# AtmegaSwitch.net
KiCad netlist of a schematic drawn in EAGLE
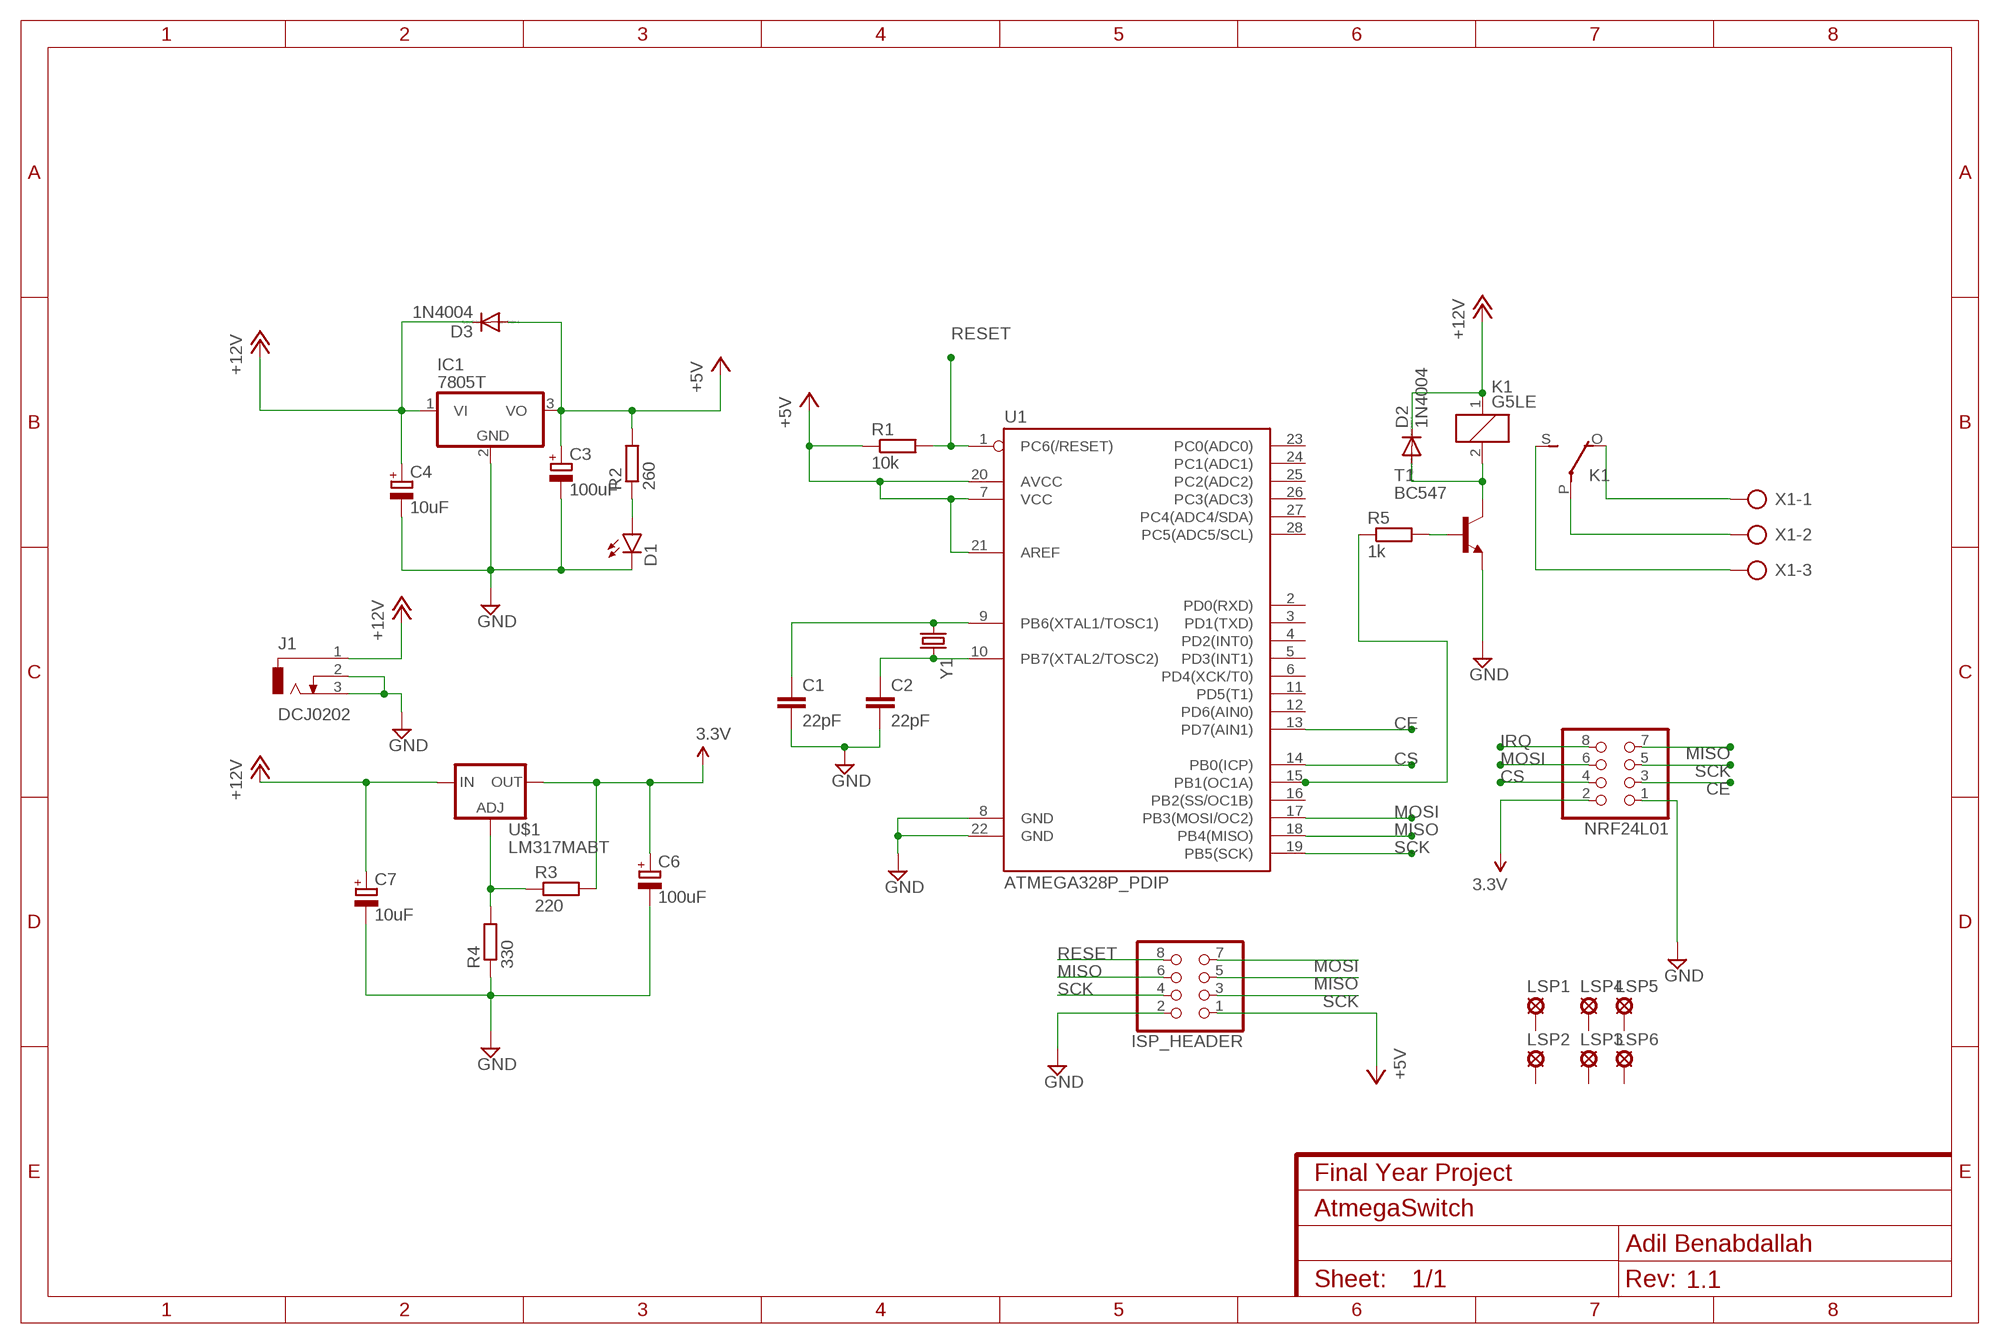
[diagram p0: schematic, sheet 1]

(export (version "E")
  (design (tool "Eeschema 10.0.6"))
  (components
    (comp (ref "C1")
      (value "22pF")
      (footprint "eagle-import:C025-025X050")
      (libsource (lib "eagle-import") (part "resistor_C-EU025-025X050"))
    )
    (comp (ref "C2")
      (value "22pF")
      (footprint "eagle-import:C025-024X044")
      (libsource (lib "eagle-import") (part "C-EU025-024X044"))
    )
    (comp (ref "C3")
      (value "100uF")
      (footprint "eagle-import:E5-6")
      (libsource (lib "eagle-import") (part "CPOL-EUE5-6"))
    )
    (comp (ref "C4")
      (value "10uF")
      (footprint "eagle-import:E5-6")
      (libsource (lib "eagle-import") (part "CPOL-EUE5-6"))
    )
    (comp (ref "C6")
      (value "100uF")
      (footprint "eagle-import:E5-6")
      (libsource (lib "eagle-import") (part "CPOL-EUE5-6"))
    )
    (comp (ref "C7")
      (value "10uF")
      (footprint "eagle-import:E5-6")
      (libsource (lib "eagle-import") (part "CPOL-EUE5-6"))
    )
    (comp (ref "D1")
      (value "LED5MM")
      (footprint "eagle-import:LED5MM")
      (libsource (lib "eagle-import") (part "LED5MM"))
    )
    (comp (ref "D2")
      (value "1N4004")
      (footprint "eagle-import:DO41-10")
      (libsource (lib "eagle-import") (part "1N4004"))
    )
    (comp (ref "D3")
      (value "1N4004")
      (footprint "eagle-import:DO41-10")
      (libsource (lib "eagle-import") (part "1N4004"))
    )
    (comp (ref "IC1")
      (value "7805T")
      (footprint "eagle-import:TO220H")
      (libsource (lib "eagle-import") (part "78T05"))
    )
    (comp (ref "ISP_HEADER")
      (value "PINHD-2X4")
      (footprint "eagle-import:2X04")
      (libsource (lib "eagle-import") (part "PINHD-2X4"))
    )
    (comp (ref "J1")
      (value "DCJ0202")
      (footprint "eagle-import:DCJ0202")
      (libsource (lib "eagle-import") (part "DCJ0202"))
    )
    (comp (ref "K1")
      (value "G5LE")
      (footprint "eagle-import:G5LE")
      (libsource (lib "eagle-import") (part "G5LE"))
    )
    (comp (ref "LSP1")
      (value "LSP10")
      (footprint "eagle-import:LSP10")
      (libsource (lib "eagle-import") (part "LSP10"))
    )
    (comp (ref "LSP2")
      (value "LSP10")
      (footprint "eagle-import:LSP10")
      (libsource (lib "eagle-import") (part "LSP10"))
    )
    (comp (ref "LSP3")
      (value "LSP10")
      (footprint "eagle-import:LSP10")
      (libsource (lib "eagle-import") (part "LSP10"))
    )
    (comp (ref "LSP4")
      (value "LSP10")
      (footprint "eagle-import:LSP10")
      (libsource (lib "eagle-import") (part "LSP10"))
    )
    (comp (ref "LSP5")
      (value "LSP10")
      (footprint "eagle-import:LSP10")
      (libsource (lib "eagle-import") (part "LSP10"))
    )
    (comp (ref "LSP6")
      (value "LSP10")
      (footprint "eagle-import:LSP10")
      (libsource (lib "eagle-import") (part "LSP10"))
    )
    (comp (ref "NRF24L01")
      (value "PINHD-2X4")
      (footprint "eagle-import:2X04")
      (libsource (lib "eagle-import") (part "PINHD-2X4"))
    )
    (comp (ref "R1")
      (value "10k")
      (footprint "eagle-import:0204_7")
      (libsource (lib "eagle-import") (part "R-EU_0204/7"))
    )
    (comp (ref "R2")
      (value "260")
      (footprint "eagle-import:0204_7")
      (libsource (lib "eagle-import") (part "R-EU_0204/7"))
    )
    (comp (ref "R3")
      (value "220")
      (footprint "eagle-import:0204_7")
      (libsource (lib "eagle-import") (part "R-EU_0204/7"))
    )
    (comp (ref "R4")
      (value "330")
      (footprint "eagle-import:0204_7")
      (libsource (lib "eagle-import") (part "R-EU_0204/7"))
    )
    (comp (ref "R5")
      (value "1k")
      (footprint "eagle-import:0204_7")
      (libsource (lib "eagle-import") (part "R-EU_0204/7"))
    )
    (comp (ref "T1")
      (value "BC547")
      (footprint "eagle-import:TO92")
      (libsource (lib "eagle-import") (part "BC547"))
    )
    (comp (ref "U$1")
      (value "LM317MABT")
      (footprint "eagle-import:TO220L1")
      (libsource (lib "eagle-import") (part "LM317?MABT"))
    )
    (comp (ref "U1")
      (value "ATMEGA328P_PDIP")
      (footprint "eagle-import:DIL28-3")
      (libsource (lib "eagle-import") (part "ATMEGA328P_PDIP"))
    )
    (comp (ref "X1")
      (value "AK500/3-H")
      (footprint "eagle-import:AK500_3-H")
      (libsource (lib "eagle-import") (part "AK500/3-H"))
    )
    (comp (ref "Y1")
      (value "CRYSTALHC49US")
      (footprint "eagle-import:HC49US")
      (libsource (lib "eagle-import") (part "CRYSTALHC49US"))
    )
  )
  (nets
    (net (code "1") (name "+5V") (class "Default")
      (node (ref "C3") (pin "+") (pinfunction "+_+") (pintype "passive"))
      (node (ref "D3") (pin "A") (pinfunction "A_A") (pintype "passive"))
      (node (ref "IC1") (pin "3") (pinfunction "VO_3") (pintype "passive"))
      (node (ref "ISP_HEADER") (pin "1") (pinfunction "1_1") (pintype "passive"))
      (node (ref "R1") (pin "1") (pinfunction "1_1") (pintype "passive"))
      (node (ref "R2") (pin "2") (pinfunction "2_2") (pintype "passive"))
      (node (ref "U1") (pin "20") (pinfunction "AVCC_20") (pintype "bidirectional"))
      (node (ref "U1") (pin "21") (pinfunction "AREF_21") (pintype "bidirectional"))
      (node (ref "U1") (pin "7") (pinfunction "VCC_7") (pintype "bidirectional"))
    )
    (net (code "2") (name "+12V") (class "Default")
      (node (ref "C4") (pin "+") (pinfunction "+_+") (pintype "passive"))
      (node (ref "C7") (pin "+") (pinfunction "+_+") (pintype "passive"))
      (node (ref "D2") (pin "C") (pinfunction "C_C") (pintype "passive"))
      (node (ref "D3") (pin "C") (pinfunction "C_C") (pintype "passive"))
      (node (ref "IC1") (pin "1") (pinfunction "VI_1") (pintype "input"))
      (node (ref "J1") (pin "1") (pinfunction "1_1") (pintype "passive"))
      (node (ref "K1") (pin "1") (pinfunction "1_1") (pintype "passive"))
      (node (ref "U$1") (pin "3") (pinfunction "IN_3") (pintype "input"))
    )
    (net (code "3") (name "/CE") (class "Default")
      (node (ref "NRF24L01") (pin "3") (pinfunction "3_3") (pintype "passive"))
      (node (ref "U1") (pin "13") (pinfunction "PD7(AIN1)_13") (pintype "bidirectional"))
    )
    (net (code "4") (name "/CS") (class "Default")
      (node (ref "NRF24L01") (pin "4") (pinfunction "4_4") (pintype "passive"))
      (node (ref "U1") (pin "14") (pinfunction "PB0(ICP)_14") (pintype "bidirectional"))
    )
    (net (code "5") (name "/IRQ") (class "Default")
      (node (ref "NRF24L01") (pin "8") (pinfunction "8_8") (pintype "passive"))
    )
    (net (code "6") (name "/MISO") (class "Default")
      (node (ref "ISP_HEADER") (pin "5") (pinfunction "5_5") (pintype "passive"))
      (node (ref "ISP_HEADER") (pin "6") (pinfunction "6_6") (pintype "passive"))
      (node (ref "NRF24L01") (pin "7") (pinfunction "7_7") (pintype "passive"))
      (node (ref "U1") (pin "18") (pinfunction "PB4(MISO)_18") (pintype "bidirectional"))
    )
    (net (code "7") (name "/MOSI") (class "Default")
      (node (ref "ISP_HEADER") (pin "7") (pinfunction "7_7") (pintype "passive"))
      (node (ref "NRF24L01") (pin "6") (pinfunction "6_6") (pintype "passive"))
      (node (ref "U1") (pin "17") (pinfunction "PB3(MOSI/OC2)_17") (pintype "bidirectional"))
    )
    (net (code "8") (name "/RESET") (class "Default")
      (node (ref "ISP_HEADER") (pin "8") (pinfunction "8_8") (pintype "passive"))
      (node (ref "R1") (pin "2") (pinfunction "2_2") (pintype "passive"))
      (node (ref "U1") (pin "1") (pinfunction "PC6(/RESET)_1") (pintype "bidirectional"))
    )
    (net (code "9") (name "/SCK") (class "Default")
      (node (ref "ISP_HEADER") (pin "3") (pinfunction "3_3") (pintype "passive"))
      (node (ref "ISP_HEADER") (pin "4") (pinfunction "4_4") (pintype "passive"))
      (node (ref "NRF24L01") (pin "5") (pinfunction "5_5") (pintype "passive"))
      (node (ref "U1") (pin "19") (pinfunction "PB5(SCK)_19") (pintype "bidirectional"))
    )
    (net (code "10") (name "3.3V") (class "Default")
      (node (ref "C6") (pin "+") (pinfunction "+_+") (pintype "passive"))
      (node (ref "NRF24L01") (pin "2") (pinfunction "2_2") (pintype "passive"))
      (node (ref "R3") (pin "2") (pinfunction "2_2") (pintype "passive"))
      (node (ref "U$1") (pin "2") (pinfunction "OUT_2") (pintype "passive"))
    )
    (net (code "11") (name "GND") (class "Default")
      (node (ref "C1") (pin "2") (pinfunction "2_2") (pintype "passive"))
      (node (ref "C2") (pin "2") (pinfunction "2_2") (pintype "passive"))
      (node (ref "C3") (pin "-") (pinfunction "-_-") (pintype "passive"))
      (node (ref "C4") (pin "-") (pinfunction "-_-") (pintype "passive"))
      (node (ref "C6") (pin "-") (pinfunction "-_-") (pintype "passive"))
      (node (ref "C7") (pin "-") (pinfunction "-_-") (pintype "passive"))
      (node (ref "D1") (pin "K") (pinfunction "C_K") (pintype "passive"))
      (node (ref "IC1") (pin "2") (pinfunction "GND_2") (pintype "passive"))
      (node (ref "ISP_HEADER") (pin "2") (pinfunction "2_2") (pintype "passive"))
      (node (ref "J1") (pin "2") (pinfunction "2_2") (pintype "passive"))
      (node (ref "J1") (pin "3") (pinfunction "3_3") (pintype "passive"))
      (node (ref "NRF24L01") (pin "1") (pinfunction "1_1") (pintype "passive"))
      (node (ref "R4") (pin "1") (pinfunction "1_1") (pintype "passive"))
      (node (ref "T1") (pin "1") (pinfunction "E_1") (pintype "passive"))
      (node (ref "U1") (pin "22") (pinfunction "GND_22") (pintype "bidirectional"))
      (node (ref "U1") (pin "8") (pinfunction "GND_8") (pintype "bidirectional"))
    )
    (net (code "12") (name "Net-(D1-PadA)") (class "Default")
      (node (ref "D1") (pin "A") (pinfunction "A_A") (pintype "passive"))
      (node (ref "R2") (pin "1") (pinfunction "1_1") (pintype "passive"))
    )
    (net (code "13") (name "Net-(T1-B)") (class "Default")
      (node (ref "R5") (pin "2") (pinfunction "2_2") (pintype "passive"))
      (node (ref "T1") (pin "2") (pinfunction "B_2") (pintype "passive"))
    )
    (net (code "14") (name "Net-(T1-C)") (class "Default")
      (node (ref "D2") (pin "A") (pinfunction "A_A") (pintype "passive"))
      (node (ref "K1") (pin "2") (pinfunction "2_2") (pintype "passive"))
      (node (ref "T1") (pin "3") (pinfunction "C_3") (pintype "passive"))
    )
    (net (code "15") (name "Net-(U$1-ADJ)") (class "Default")
      (node (ref "R3") (pin "1") (pinfunction "1_1") (pintype "passive"))
      (node (ref "R4") (pin "2") (pinfunction "2_2") (pintype "passive"))
      (node (ref "U$1") (pin "1") (pinfunction "ADJ_1") (pintype "input"))
    )
    (net (code "16") (name "Net-(U1-PB1(OC1A))") (class "Default")
      (node (ref "R5") (pin "1") (pinfunction "1_1") (pintype "passive"))
      (node (ref "U1") (pin "15") (pinfunction "PB1(OC1A)_15") (pintype "bidirectional"))
    )
    (net (code "17") (name "Net-(U1-PB6(XTAL1{slash}TOSC1))") (class "Default")
      (node (ref "C1") (pin "1") (pinfunction "1_1") (pintype "passive"))
      (node (ref "U1") (pin "9") (pinfunction "PB6(XTAL1/TOSC1)_9") (pintype "bidirectional"))
      (node (ref "Y1") (pin "1") (pinfunction "1_1") (pintype "passive"))
    )
    (net (code "18") (name "Net-(U1-PB7(XTAL2{slash}TOSC2))") (class "Default")
      (node (ref "C2") (pin "1") (pinfunction "1_1") (pintype "passive"))
      (node (ref "U1") (pin "10") (pinfunction "PB7(XTAL2/TOSC2)_10") (pintype "bidirectional"))
      (node (ref "Y1") (pin "2") (pinfunction "2_2") (pintype "passive"))
    )
    (net (code "19") (name "Net-(X1A-KL)") (class "Default")
      (node (ref "K1") (pin "O") (pinfunction "O_O") (pintype "passive"))
      (node (ref "X1") (pin "1") (pinfunction "KL_1") (pintype "passive"))
    )
    (net (code "20") (name "Net-(X1B-KL)") (class "Default")
      (node (ref "K1") (pin "P") (pinfunction "P_P") (pintype "passive"))
      (node (ref "X1") (pin "2") (pinfunction "KL_2") (pintype "passive"))
    )
    (net (code "21") (name "Net-(X1C-KL)") (class "Default")
      (node (ref "K1") (pin "S") (pinfunction "S_S") (pintype "passive"))
      (node (ref "X1") (pin "3") (pinfunction "KL_3") (pintype "passive"))
    )
    (net (code "22") (name "unconnected-(LSP1-PadMP)") (class "Default")
      (node (ref "LSP1") (pin "MP") (pinfunction "MP_MP") (pintype "passive"))
    )
    (net (code "23") (name "unconnected-(LSP2-PadMP)") (class "Default")
      (node (ref "LSP2") (pin "MP") (pinfunction "MP_MP") (pintype "passive"))
    )
    (net (code "24") (name "unconnected-(LSP3-PadMP)") (class "Default")
      (node (ref "LSP3") (pin "MP") (pinfunction "MP_MP") (pintype "passive"))
    )
    (net (code "25") (name "unconnected-(LSP4-PadMP)") (class "Default")
      (node (ref "LSP4") (pin "MP") (pinfunction "MP_MP") (pintype "passive"))
    )
    (net (code "26") (name "unconnected-(LSP5-PadMP)") (class "Default")
      (node (ref "LSP5") (pin "MP") (pinfunction "MP_MP") (pintype "passive"))
    )
    (net (code "27") (name "unconnected-(LSP6-PadMP)") (class "Default")
      (node (ref "LSP6") (pin "MP") (pinfunction "MP_MP") (pintype "passive"))
    )
    (net (code "28") (name "unconnected-(U1-PB2(SS{slash}OC1B)-Pad16)") (class "Default")
      (node (ref "U1") (pin "16") (pinfunction "PB2(SS/OC1B)_16") (pintype "bidirectional"))
    )
    (net (code "29") (name "unconnected-(U1-PC0(ADC0)-Pad23)") (class "Default")
      (node (ref "U1") (pin "23") (pinfunction "PC0(ADC0)_23") (pintype "bidirectional"))
    )
    (net (code "30") (name "unconnected-(U1-PC1(ADC1)-Pad24)") (class "Default")
      (node (ref "U1") (pin "24") (pinfunction "PC1(ADC1)_24") (pintype "bidirectional"))
    )
    (net (code "31") (name "unconnected-(U1-PC2(ADC2)-Pad25)") (class "Default")
      (node (ref "U1") (pin "25") (pinfunction "PC2(ADC2)_25") (pintype "bidirectional"))
    )
    (net (code "32") (name "unconnected-(U1-PC3(ADC3)-Pad26)") (class "Default")
      (node (ref "U1") (pin "26") (pinfunction "PC3(ADC3)_26") (pintype "bidirectional"))
    )
    (net (code "33") (name "unconnected-(U1-PC4(ADC4{slash}SDA)-Pad27)") (class "Default")
      (node (ref "U1") (pin "27") (pinfunction "PC4(ADC4/SDA)_27") (pintype "bidirectional"))
    )
    (net (code "34") (name "unconnected-(U1-PC5(ADC5{slash}SCL)-Pad28)") (class "Default")
      (node (ref "U1") (pin "28") (pinfunction "PC5(ADC5/SCL)_28") (pintype "bidirectional"))
    )
    (net (code "35") (name "unconnected-(U1-PD0(RXD)-Pad2)") (class "Default")
      (node (ref "U1") (pin "2") (pinfunction "PD0(RXD)_2") (pintype "bidirectional"))
    )
    (net (code "36") (name "unconnected-(U1-PD1(TXD)-Pad3)") (class "Default")
      (node (ref "U1") (pin "3") (pinfunction "PD1(TXD)_3") (pintype "bidirectional"))
    )
    (net (code "37") (name "unconnected-(U1-PD2(INT0)-Pad4)") (class "Default")
      (node (ref "U1") (pin "4") (pinfunction "PD2(INT0)_4") (pintype "bidirectional"))
    )
    (net (code "38") (name "unconnected-(U1-PD3(INT1)-Pad5)") (class "Default")
      (node (ref "U1") (pin "5") (pinfunction "PD3(INT1)_5") (pintype "bidirectional"))
    )
    (net (code "39") (name "unconnected-(U1-PD4(XCK{slash}T0)-Pad6)") (class "Default")
      (node (ref "U1") (pin "6") (pinfunction "PD4(XCK/T0)_6") (pintype "bidirectional"))
    )
    (net (code "40") (name "unconnected-(U1-PD5(T1)-Pad11)") (class "Default")
      (node (ref "U1") (pin "11") (pinfunction "PD5(T1)_11") (pintype "bidirectional"))
    )
    (net (code "41") (name "unconnected-(U1-PD6(AIN0)-Pad12)") (class "Default")
      (node (ref "U1") (pin "12") (pinfunction "PD6(AIN0)_12") (pintype "bidirectional"))
    )
  )
)
